# Sheet2_3.net
KiCad netlist of a schematic drawn in Altium Designer
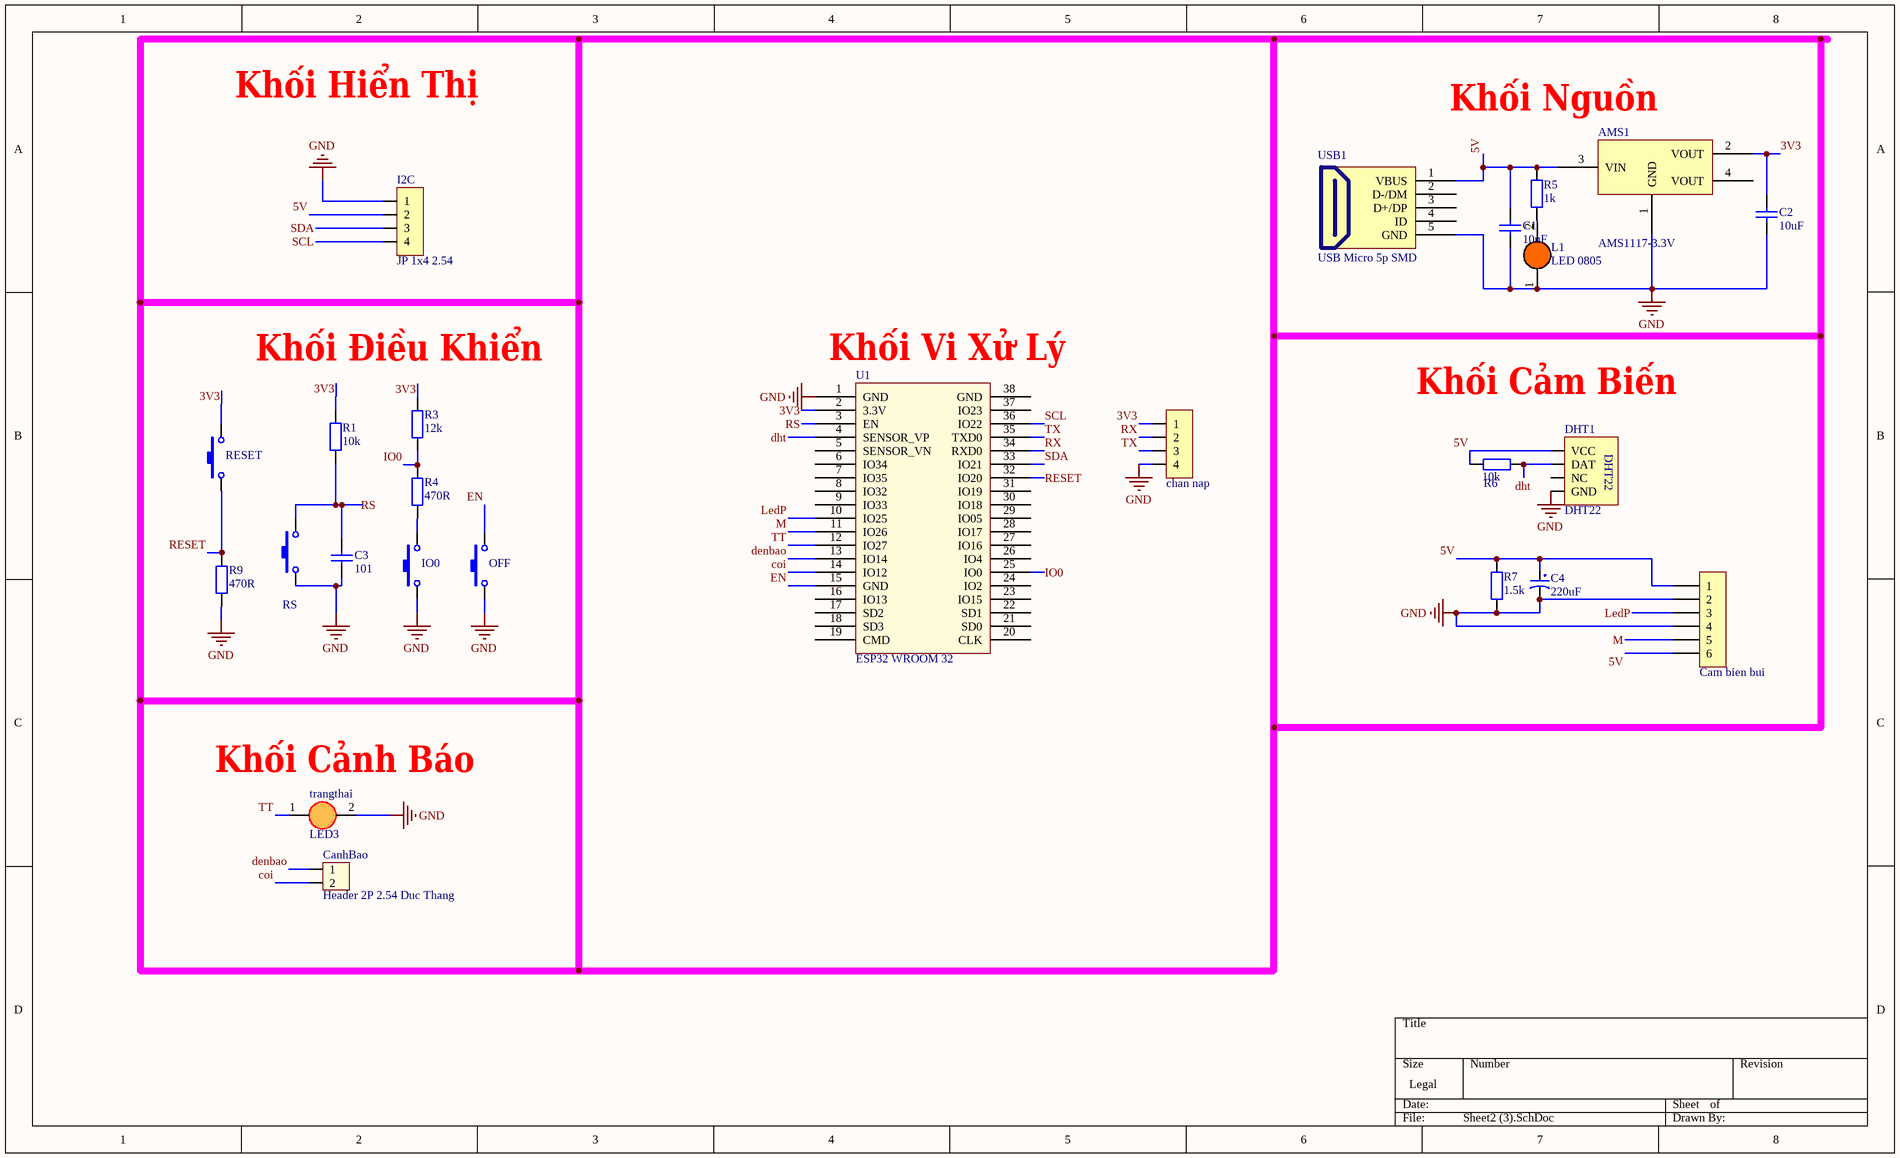
[diagram p0: Sheet2 (3).SchDoc]

(export (version "E")
  (design (tool "Eeschema 10.0.6"))
  (components
    (comp (ref "AMS1")
      (value "AMS1117-3.3V")
      (footprint "SOT223")
      (description "Dán")
      (libsource (lib "Altium_Lib_by_KhueNguyenCreator") (part "AMS1117 SMD"))
    )
    (comp (ref "C1")
      (value "10uF")
      (footprint "tu 0805")
      (description "Dán")
      (libsource (lib "Altium_Lib_by_KhueNguyenCreator") (part "Tu 0805 10pF 50V 10%"))
    )
    (comp (ref "C2")
      (value "10uF")
      (footprint "tu 0805")
      (description "Dán")
      (libsource (lib "Altium_Lib_by_KhueNguyenCreator") (part "Tu 0805 10pF 50V 10%"))
    )
    (comp (ref "C3")
      (value "101")
      (footprint "tu 0805")
      (description "Dán")
      (libsource (lib "Altium_Lib_by_KhueNguyenCreator") (part "Tu 0805 101 50V 20%"))
    )
    (comp (ref "C4")
      (value "220uF")
      (footprint "Tu hoa 5mm")
      (description "Cắm")
      (libsource (lib "Altium_Lib_by_KhueNguyenCreator") (part "Tu Hoa 220uF 16V 6x11"))
    )
    (comp (ref "Cam bien bui")
      (value "Cam bien bui")
      (footprint "XH2.54M-6")
      (description "Cắm")
      (libsource (lib "Altium_Lib_by_KhueNguyenCreator") (part "Header 6P 2.54 Duc Thang"))
    )
    (comp (ref "CanhBao")
      (value "Header 2P 2.54 Duc Thang")
      (footprint "XH2.54M-2")
      (description "Cắm")
      (libsource (lib "Altium_Lib_by_KhueNguyenCreator") (part "Header 2P 2.54 Duc Thang"))
    )
    (comp (ref "DHT1")
      (value "DHT22")
      (footprint "DHT22")
      (fields
        (field (name "MANUFACTURER") "Würth Elektronik eiSos GmbH")
        (field (name "PARTNO") "613004143121")
        (field (name "CREATED BY") "Karrer Zheng")
      )
      (libsource (lib "LIBRARY") (part "DHT22"))
    )
    (comp (ref "I2C")
      (value "JP 1x4 2.54")
      (footprint "JP 1x4 DT")
      (description "Cắm")
      (libsource (lib "Altium_Lib_by_KhueNguyenCreator") (part "JP 1x4 2.54 Duc Thang"))
    )
    (comp (ref "IO0")
      (value "Nut Nhan 2 Chan SMD 3x6x2.5")
      (footprint "Nut Nhan 2 Chan SMD 3x6x2.5")
      (libsource (lib "Altium_Lib_by_KhueNguyenCreator") (part "Nut Nhan 2 Chan SMD 3x6x2.5"))
    )
    (comp (ref "JP1")
      (value "chan nap")
      (footprint "JP 1x4 CT")
      (description "Cắm")
      (libsource (lib "Altium_Lib_by_KhueNguyenCreator") (part "JP 1x4 2.54 Cai Thang"))
    )
    (comp (ref "L1")
      (value "LED 0805")
      (footprint "LED-0805-Orange")
      (description "Dán")
      (libsource (lib "Altium_Lib_by_KhueNguyenCreator") (part "LED 0805 Cam"))
    )
    (comp (ref "OFF")
      (value "Nut Nhan 2 Chan SMD 3x6x2.5")
      (footprint "Nut Nhan 2 Chan SMD 3x6x2.5")
      (libsource (lib "Altium_Lib_by_KhueNguyenCreator") (part "Nut Nhan 2 Chan SMD 3x6x2.5"))
    )
    (comp (ref "R1")
      (value "10k")
      (footprint "tro smd 0805")
      (description "Dán")
      (libsource (lib "Altium_Lib_by_KhueNguyenCreator") (part "Tro 0805 1% 10k"))
    )
    (comp (ref "R3")
      (value "12k")
      (footprint "tro smd 0805")
      (description "Dán")
      (libsource (lib "Altium_Lib_by_KhueNguyenCreator") (part "Tro 0805 5% 12k"))
    )
    (comp (ref "R4")
      (value "470R")
      (footprint "Tro SMD 0805")
      (description "Dán")
      (libsource (lib "Altium_Lib_by_KhueNguyenCreator") (part "Tro 0805 5% 470R"))
    )
    (comp (ref "R5")
      (value "1k")
      (footprint "tro smd 0805")
      (description "Dán")
      (libsource (lib "Altium_Lib_by_KhueNguyenCreator") (part "Tro 0805 1% 1k"))
    )
    (comp (ref "R6")
      (value "10k")
      (footprint "tro smd 0805")
      (description "Dán")
      (libsource (lib "Altium_Lib_by_KhueNguyenCreator") (part "Tro 0805 5% 10k"))
    )
    (comp (ref "R7")
      (value "1.5k")
      (footprint "tro vach 1/4w")
      (description "Cắm")
      (libsource (lib "Altium_Lib_by_KhueNguyenCreator") (part "Tro Vach 1/4W 5% 1.5k"))
    )
    (comp (ref "R9")
      (value "470R")
      (footprint "Tro SMD 0805")
      (description "Dán")
      (libsource (lib "Altium_Lib_by_KhueNguyenCreator") (part "Tro 0805 5% 470R"))
    )
    (comp (ref "RESET")
      (value "Nut Nhan 2 Chan SMD 3x6x2.5")
      (footprint "Nut Nhan 2 Chan SMD 3x6x2.5")
      (libsource (lib "Altium_Lib_by_KhueNguyenCreator") (part "Nut Nhan 2 Chan SMD 3x6x2.5"))
    )
    (comp (ref "RS")
      (value "Nut Nhan 2 Chan SMD 3x6x2.5")
      (footprint "Nut Nhan 2 Chan SMD 3x6x2.5")
      (libsource (lib "Altium_Lib_by_KhueNguyenCreator") (part "Nut Nhan 2 Chan SMD 3x6x2.5"))
    )
    (comp (ref "trangthai")
      (value "LED3")
      (footprint "LED3mm")
      (description "LED 3mm")
      (libsource (lib "Cty1") (part "LED 3mm"))
    )
    (comp (ref "U1")
      (value "ESP32 WROOM 32")
      (footprint "ESP32-WROOM-32D")
      (libsource (lib "Altium_Lib_by_KhueNguyenCreator") (part "ESP32 WROOM 32"))
    )
    (comp (ref "USB1")
      (value "USB Micro 5p SMD")
      (footprint "USB Micro 5p SMD")
      (description "USB Type B")
      (libsource (lib "Altium_Lib_by_KhueNguyenCreator") (part "USB Micro 5p SMD"))
    )
  )
  (nets
    (net (code "1") (name "/3V3") (class "Default")
      (node (ref "AMS1") (pin "2") (pinfunction "VOUT_2") (pintype "passive"))
      (node (ref "C2") (pin "1") (pinfunction "1_1") (pintype "passive"))
      (node (ref "JP1") (pin "1") (pinfunction "1_1") (pintype "passive"))
      (node (ref "R1") (pin "2") (pinfunction "2_2") (pintype "passive"))
      (node (ref "R3") (pin "2") (pinfunction "2_2") (pintype "passive"))
      (node (ref "RESET") (pin "2") (pinfunction "2_2") (pintype "passive"))
      (node (ref "U1") (pin "2") (pinfunction "3.3V_2") (pintype "passive"))
    )
    (net (code "2") (name "/5V") (class "Default")
      (node (ref "AMS1") (pin "3") (pinfunction "VIN_3") (pintype "passive"))
      (node (ref "C1") (pin "1") (pinfunction "1_1") (pintype "passive"))
      (node (ref "C4") (pin "1") (pinfunction "1_1") (pintype "passive"))
      (node (ref "Cam bien bui") (pin "1") (pinfunction "1_1") (pintype "passive"))
      (node (ref "Cam bien bui") (pin "6") (pinfunction "6_6") (pintype "passive"))
      (node (ref "DHT1") (pin "1") (pinfunction "VCC_1") (pintype "passive"))
      (node (ref "I2C") (pin "2") (pinfunction "2_2") (pintype "passive"))
      (node (ref "R5") (pin "2") (pinfunction "2_2") (pintype "passive"))
      (node (ref "R6") (pin "1") (pinfunction "1_1") (pintype "passive"))
      (node (ref "R7") (pin "2") (pinfunction "2_2") (pintype "passive"))
      (node (ref "USB1") (pin "1") (pinfunction "VBUS_1") (pintype "passive"))
    )
    (net (code "3") (name "/EN") (class "Default")
      (node (ref "OFF") (pin "2") (pinfunction "2_2") (pintype "passive"))
      (node (ref "U1") (pin "15") (pinfunction "GND_15") (pintype "passive"))
    )
    (net (code "4") (name "/IO0") (class "Default")
      (node (ref "R3") (pin "1") (pinfunction "1_1") (pintype "passive"))
      (node (ref "R4") (pin "2") (pinfunction "2_2") (pintype "passive"))
      (node (ref "U1") (pin "25") (pinfunction "IO0_25") (pintype "passive"))
    )
    (net (code "5") (name "/LedP") (class "Default")
      (node (ref "Cam bien bui") (pin "3") (pinfunction "3_3") (pintype "passive"))
      (node (ref "U1") (pin "10") (pinfunction "IO25_10") (pintype "passive"))
    )
    (net (code "6") (name "/M") (class "Default")
      (node (ref "Cam bien bui") (pin "5") (pinfunction "5_5") (pintype "passive"))
      (node (ref "U1") (pin "11") (pinfunction "IO26_11") (pintype "passive"))
    )
    (net (code "7") (name "/RESET") (class "Default")
      (node (ref "R9") (pin "2") (pinfunction "2_2") (pintype "passive"))
      (node (ref "RESET") (pin "1") (pinfunction "1_1") (pintype "passive"))
      (node (ref "U1") (pin "32") (pinfunction "IO20_32") (pintype "passive"))
    )
    (net (code "8") (name "/RS") (class "Default")
      (node (ref "C3") (pin "1") (pinfunction "1_1") (pintype "passive"))
      (node (ref "R1") (pin "1") (pinfunction "1_1") (pintype "passive"))
      (node (ref "RS") (pin "2") (pinfunction "2_2") (pintype "passive"))
      (node (ref "U1") (pin "3") (pinfunction "EN_3") (pintype "passive"))
    )
    (net (code "9") (name "/RX") (class "Default")
      (node (ref "JP1") (pin "2") (pinfunction "2_2") (pintype "passive"))
      (node (ref "U1") (pin "34") (pinfunction "RXD0_34") (pintype "passive"))
    )
    (net (code "10") (name "/SCL") (class "Default")
      (node (ref "I2C") (pin "4") (pinfunction "4_4") (pintype "passive"))
      (node (ref "U1") (pin "36") (pinfunction "IO22_36") (pintype "passive"))
    )
    (net (code "11") (name "/SDA") (class "Default")
      (node (ref "I2C") (pin "3") (pinfunction "3_3") (pintype "passive"))
      (node (ref "U1") (pin "33") (pinfunction "IO21_33") (pintype "passive"))
    )
    (net (code "12") (name "/TT") (class "Default")
      (node (ref "U1") (pin "12") (pinfunction "IO27_12") (pintype "passive"))
      (node (ref "trangthai") (pin "1") (pinfunction "A_1") (pintype "passive"))
    )
    (net (code "13") (name "/TX") (class "Default")
      (node (ref "JP1") (pin "3") (pinfunction "3_3") (pintype "passive"))
      (node (ref "U1") (pin "35") (pinfunction "TXD0_35") (pintype "passive"))
    )
    (net (code "14") (name "/coi") (class "Default")
      (node (ref "CanhBao") (pin "2") (pinfunction "2_2") (pintype "passive"))
      (node (ref "U1") (pin "14") (pinfunction "IO12_14") (pintype "passive"))
    )
    (net (code "15") (name "/denbao") (class "Default")
      (node (ref "CanhBao") (pin "1") (pinfunction "1_1") (pintype "passive"))
      (node (ref "U1") (pin "13") (pinfunction "IO14_13") (pintype "passive"))
    )
    (net (code "16") (name "/dht") (class "Default")
      (node (ref "DHT1") (pin "2") (pinfunction "DAT_2") (pintype "passive"))
      (node (ref "R6") (pin "2") (pinfunction "2_2") (pintype "passive"))
      (node (ref "U1") (pin "4") (pinfunction "SENSOR_VP_4") (pintype "passive"))
    )
    (net (code "17") (name "GND") (class "Default")
      (node (ref "AMS1") (pin "1") (pinfunction "GND_1") (pintype "passive"))
      (node (ref "C1") (pin "2") (pinfunction "2_2") (pintype "passive"))
      (node (ref "C2") (pin "2") (pinfunction "2_2") (pintype "passive"))
      (node (ref "C3") (pin "2") (pinfunction "2_2") (pintype "passive"))
      (node (ref "C4") (pin "2") (pinfunction "2_2") (pintype "passive"))
      (node (ref "Cam bien bui") (pin "2") (pinfunction "2_2") (pintype "passive"))
      (node (ref "Cam bien bui") (pin "4") (pinfunction "4_4") (pintype "passive"))
      (node (ref "DHT1") (pin "4") (pinfunction "GND_4") (pintype "passive"))
      (node (ref "I2C") (pin "1") (pinfunction "1_1") (pintype "passive"))
      (node (ref "IO0") (pin "1") (pinfunction "1_1") (pintype "passive"))
      (node (ref "JP1") (pin "4") (pinfunction "4_4") (pintype "passive"))
      (node (ref "L1") (pin "1") (pinfunction "A_1") (pintype "passive"))
      (node (ref "OFF") (pin "1") (pinfunction "1_1") (pintype "passive"))
      (node (ref "R7") (pin "1") (pinfunction "1_1") (pintype "passive"))
      (node (ref "R9") (pin "1") (pinfunction "1_1") (pintype "passive"))
      (node (ref "RS") (pin "1") (pinfunction "1_1") (pintype "passive"))
      (node (ref "U1") (pin "1") (pinfunction "GND_1") (pintype "passive"))
      (node (ref "USB1") (pin "5") (pinfunction "GND_5") (pintype "passive"))
      (node (ref "trangthai") (pin "2") (pinfunction "K_2") (pintype "passive"))
    )
    (net (code "18") (name "Net-(IO0-Pad2)") (class "Default")
      (node (ref "IO0") (pin "2") (pinfunction "2_2") (pintype "passive"))
      (node (ref "R4") (pin "1") (pinfunction "1_1") (pintype "passive"))
    )
    (net (code "19") (name "Net-(L1-K)") (class "Default")
      (node (ref "L1") (pin "2") (pinfunction "K_2") (pintype "passive"))
      (node (ref "R5") (pin "1") (pinfunction "1_1") (pintype "passive"))
    )
    (net (code "20") (name "unconnected-(AMS1-VOUT-Pad4)") (class "Default")
      (node (ref "AMS1") (pin "4") (pinfunction "VOUT_4") (pintype "passive"))
    )
    (net (code "21") (name "unconnected-(DHT1-NC-Pad3)") (class "Default")
      (node (ref "DHT1") (pin "3") (pinfunction "NC_3") (pintype "passive"))
    )
    (net (code "22") (name "unconnected-(U1-CLK-Pad20)") (class "Default")
      (node (ref "U1") (pin "20") (pinfunction "CLK_20") (pintype "passive"))
    )
    (net (code "23") (name "unconnected-(U1-CMD-Pad19)") (class "Default")
      (node (ref "U1") (pin "19") (pinfunction "CMD_19") (pintype "passive"))
    )
    (net (code "24") (name "unconnected-(U1-GND-Pad38)") (class "Default")
      (node (ref "U1") (pin "38") (pinfunction "GND_38") (pintype "passive"))
    )
    (net (code "25") (name "unconnected-(U1-IO2-Pad24)") (class "Default")
      (node (ref "U1") (pin "24") (pinfunction "IO2_24") (pintype "passive"))
    )
    (net (code "26") (name "unconnected-(U1-IO4-Pad26)") (class "Default")
      (node (ref "U1") (pin "26") (pinfunction "IO4_26") (pintype "passive"))
    )
    (net (code "27") (name "unconnected-(U1-IO05-Pad29)") (class "Default")
      (node (ref "U1") (pin "29") (pinfunction "IO05_29") (pintype "passive"))
    )
    (net (code "28") (name "unconnected-(U1-IO13-Pad16)") (class "Default")
      (node (ref "U1") (pin "16") (pinfunction "IO13_16") (pintype "passive"))
    )
    (net (code "29") (name "unconnected-(U1-IO15-Pad23)") (class "Default")
      (node (ref "U1") (pin "23") (pinfunction "IO15_23") (pintype "passive"))
    )
    (net (code "30") (name "unconnected-(U1-IO16-Pad27)") (class "Default")
      (node (ref "U1") (pin "27") (pinfunction "IO16_27") (pintype "passive"))
    )
    (net (code "31") (name "unconnected-(U1-IO17-Pad28)") (class "Default")
      (node (ref "U1") (pin "28") (pinfunction "IO17_28") (pintype "passive"))
    )
    (net (code "32") (name "unconnected-(U1-IO18-Pad30)") (class "Default")
      (node (ref "U1") (pin "30") (pinfunction "IO18_30") (pintype "passive"))
    )
    (net (code "33") (name "unconnected-(U1-IO19-Pad31)") (class "Default")
      (node (ref "U1") (pin "31") (pinfunction "IO19_31") (pintype "passive"))
    )
    (net (code "34") (name "unconnected-(U1-IO23-Pad37)") (class "Default")
      (node (ref "U1") (pin "37") (pinfunction "IO23_37") (pintype "passive"))
    )
    (net (code "35") (name "unconnected-(U1-IO32-Pad8)") (class "Default")
      (node (ref "U1") (pin "8") (pinfunction "IO32_8") (pintype "passive"))
    )
    (net (code "36") (name "unconnected-(U1-IO33-Pad9)") (class "Default")
      (node (ref "U1") (pin "9") (pinfunction "IO33_9") (pintype "passive"))
    )
    (net (code "37") (name "unconnected-(U1-IO34-Pad6)") (class "Default")
      (node (ref "U1") (pin "6") (pinfunction "IO34_6") (pintype "passive"))
    )
    (net (code "38") (name "unconnected-(U1-IO35-Pad7)") (class "Default")
      (node (ref "U1") (pin "7") (pinfunction "IO35_7") (pintype "passive"))
    )
    (net (code "39") (name "unconnected-(U1-SD0-Pad21)") (class "Default")
      (node (ref "U1") (pin "21") (pinfunction "SD0_21") (pintype "passive"))
    )
    (net (code "40") (name "unconnected-(U1-SD1-Pad22)") (class "Default")
      (node (ref "U1") (pin "22") (pinfunction "SD1_22") (pintype "passive"))
    )
    (net (code "41") (name "unconnected-(U1-SD2-Pad17)") (class "Default")
      (node (ref "U1") (pin "17") (pinfunction "SD2_17") (pintype "passive"))
    )
    (net (code "42") (name "unconnected-(U1-SD3-Pad18)") (class "Default")
      (node (ref "U1") (pin "18") (pinfunction "SD3_18") (pintype "passive"))
    )
    (net (code "43") (name "unconnected-(U1-SENSOR_VN-Pad5)") (class "Default")
      (node (ref "U1") (pin "5") (pinfunction "SENSOR_VN_5") (pintype "passive"))
    )
    (net (code "44") (name "unconnected-(USB1-D+{slash}DP-Pad3)") (class "Default")
      (node (ref "USB1") (pin "3") (pinfunction "D+/DP_3") (pintype "passive"))
    )
    (net (code "45") (name "unconnected-(USB1-D-{slash}DM-Pad2)") (class "Default")
      (node (ref "USB1") (pin "2") (pinfunction "D-/DM_2") (pintype "passive"))
    )
    (net (code "46") (name "unconnected-(USB1-ID-Pad4)") (class "Default")
      (node (ref "USB1") (pin "4") (pinfunction "ID_4") (pintype "passive"))
    )
  )
)
